# lipo_charger.net
KiCad netlist of a schematic drawn in EAGLE
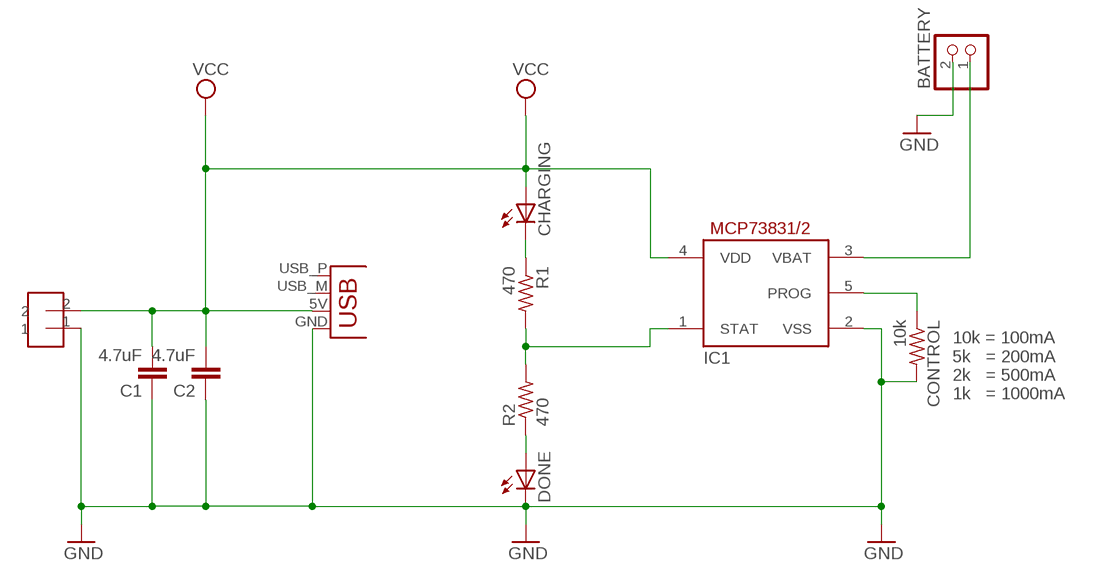
[diagram p0: schematic, sheet 1]

(export (version "E")
  (design (tool "Eeschema 10.0.6"))
  (components
    (comp (ref "BATTERY")
      (value "JST_2PIN-SMT-RA")
      (footprint "eagle-import:JST-PH-2-SMT-RA")
      (libsource (lib "eagle-import") (part "JST_2PIN-SMT-RA"))
    )
    (comp (ref "C1")
      (value "4.7uF")
      (footprint "eagle-import:0603-CAP")
      (libsource (lib "eagle-import") (part "CAP0603-CAP"))
    )
    (comp (ref "C2")
      (value "4.7uF")
      (footprint "eagle-import:0603-CAP")
      (libsource (lib "eagle-import") (part "CAP0603-CAP"))
    )
    (comp (ref "CHARGING")
      (value "LEDCHIPLED_0603")
      (footprint "eagle-import:CHIPLED_0603")
      (libsource (lib "eagle-import") (part "LEDCHIPLED_0603"))
    )
    (comp (ref "CONTROL")
      (value "10k")
      (footprint "eagle-import:R0603")
      (libsource (lib "eagle-import") (part "R-US_R0603"))
    )
    (comp (ref "DONE")
      (value "LEDCHIPLED_0603")
      (footprint "eagle-import:CHIPLED_0603")
      (libsource (lib "eagle-import") (part "LEDCHIPLED_0603"))
    )
    (comp (ref "IC1")
      (value "MCP73831/OT")
      (footprint "eagle-import:SOT23-5L")
      (libsource (lib "eagle-import") (part "MCP73831/OT"))
    )
    (comp (ref "JP1")
      (value "USBPCB")
      (footprint "eagle-import:USB-A-PCB")
      (libsource (lib "eagle-import") (part "USBPCB"))
    )
    (comp (ref "R1")
      (value "470")
      (footprint "eagle-import:R0603")
      (libsource (lib "eagle-import") (part "R-US_R0603"))
    )
    (comp (ref "R2")
      (value "470")
      (footprint "eagle-import:R0603")
      (libsource (lib "eagle-import") (part "R-US_R0603"))
    )
    (comp (ref "U$1")
      (value "HEADER-2")
      (footprint "eagle-import:HEADER-2")
      (libsource (lib "eagle-import") (part "HEADER-2"))
    )
  )
  (nets
    (net (code "1") (name "GND") (class "Default")
      (node (ref "BATTERY") (pin "2") (pinfunction "1_2") (pintype "passive"))
      (node (ref "C1") (pin "1") (pinfunction "1_1") (pintype "passive"))
      (node (ref "C2") (pin "1") (pinfunction "1_1") (pintype "passive"))
      (node (ref "CONTROL") (pin "2") (pinfunction "2_2") (pintype "passive"))
      (node (ref "DONE") (pin "C") (pinfunction "C_C") (pintype "passive"))
      (node (ref "IC1") (pin "2") (pinfunction "VSS_2") (pintype "power_in"))
      (node (ref "JP1") (pin "GND") (pinfunction "GND_GND") (pintype "bidirectional"))
      (node (ref "U$1") (pin "1") (pinfunction "1_1") (pintype "bidirectional"))
    )
    (net (code "2") (name "Net-(BATTERY-2)") (class "Default")
      (node (ref "BATTERY") (pin "1") (pinfunction "2_1") (pintype "passive"))
      (node (ref "IC1") (pin "3") (pinfunction "VBAT_3") (pintype "bidirectional"))
    )
    (net (code "3") (name "Net-(CHARGING-PadC)") (class "Default")
      (node (ref "CHARGING") (pin "C") (pinfunction "C_C") (pintype "passive"))
      (node (ref "R1") (pin "1") (pinfunction "1_1") (pintype "passive"))
    )
    (net (code "4") (name "Net-(DONE-PadA)") (class "Default")
      (node (ref "DONE") (pin "A") (pinfunction "A_A") (pintype "passive"))
      (node (ref "R2") (pin "1") (pinfunction "1_1") (pintype "passive"))
    )
    (net (code "5") (name "Net-(IC1-PROG)") (class "Default")
      (node (ref "CONTROL") (pin "1") (pinfunction "1_1") (pintype "passive"))
      (node (ref "IC1") (pin "5") (pinfunction "PROG_5") (pintype "input"))
    )
    (net (code "6") (name "Net-(IC1-STAT)") (class "Default")
      (node (ref "IC1") (pin "1") (pinfunction "STAT_1") (pintype "output"))
      (node (ref "R1") (pin "2") (pinfunction "2_2") (pintype "passive"))
      (node (ref "R2") (pin "2") (pinfunction "2_2") (pintype "passive"))
    )
    (net (code "7") (name "VCC") (class "Default")
      (node (ref "C1") (pin "2") (pinfunction "2_2") (pintype "passive"))
      (node (ref "C2") (pin "2") (pinfunction "2_2") (pintype "passive"))
      (node (ref "CHARGING") (pin "A") (pinfunction "A_A") (pintype "passive"))
      (node (ref "IC1") (pin "4") (pinfunction "VDD_4") (pintype "power_in"))
      (node (ref "JP1") (pin "5V") (pinfunction "VBUS_5V") (pintype "bidirectional"))
      (node (ref "U$1") (pin "2") (pinfunction "2_2") (pintype "bidirectional"))
    )
    (net (code "8") (name "unconnected-(JP1-D+-PadUSB_P)") (class "Default")
      (node (ref "JP1") (pin "USB_P") (pinfunction "D+_USB_P") (pintype "bidirectional"))
    )
    (net (code "9") (name "unconnected-(JP1-D--PadUSB_M)") (class "Default")
      (node (ref "JP1") (pin "USB_M") (pinfunction "D-_USB_M") (pintype "bidirectional"))
    )
  )
)
